# imu_middle.net
KiCad netlist of a schematic drawn in EAGLE
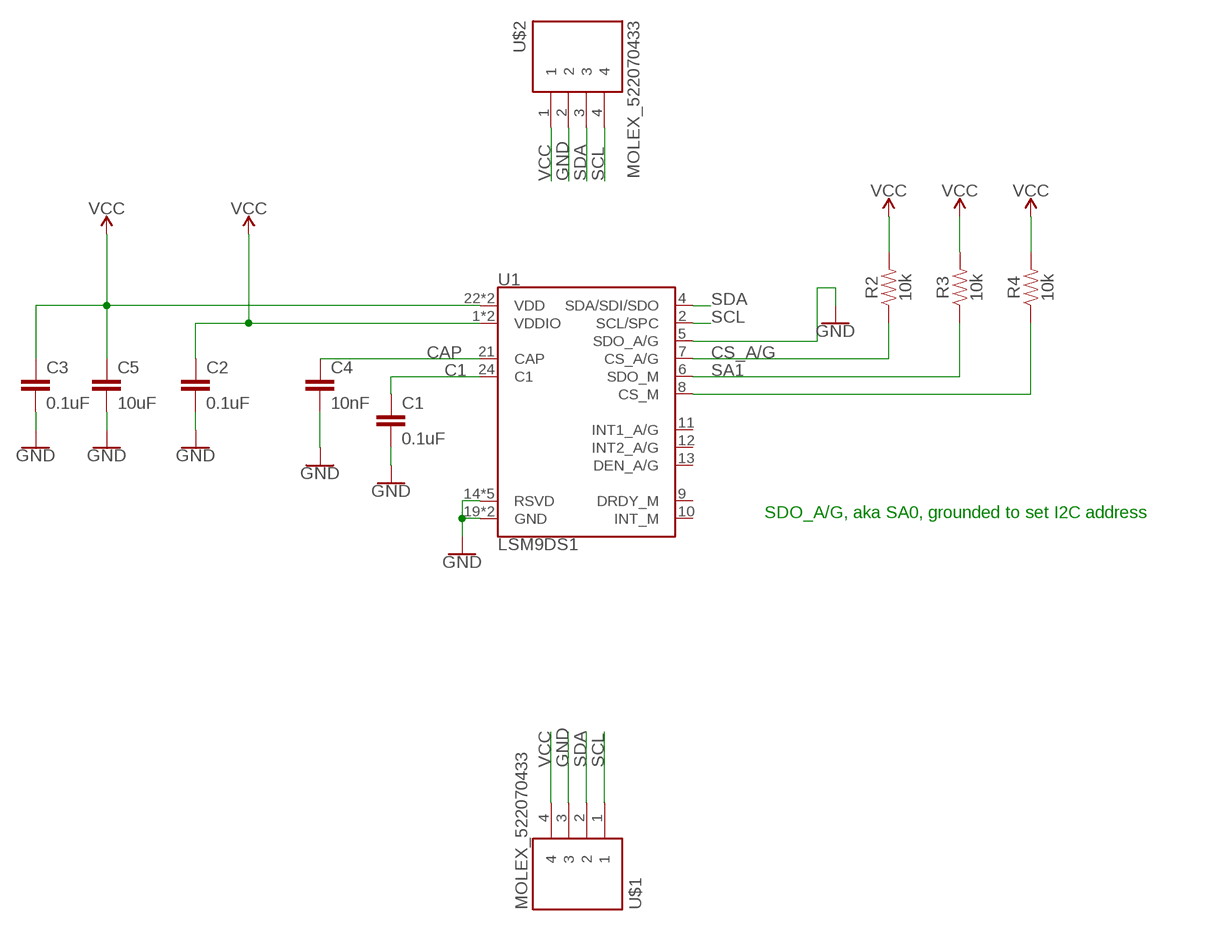
[diagram p0: schematic, sheet 1]

(export (version "E")
  (design (tool "Eeschema 10.0.6"))
  (components
    (comp (ref "C1")
      (value "0.1uF")
      (footprint "eagle-import:0603")
      (libsource (lib "eagle-import") (part "0.1UF-0603-25V-(+80/-20%)"))
    )
    (comp (ref "C2")
      (value "0.1uF")
      (footprint "eagle-import:0603")
      (libsource (lib "eagle-import") (part "0.1UF-0603-25V-(+80/-20%)"))
    )
    (comp (ref "C3")
      (value "0.1uF")
      (footprint "eagle-import:0603")
      (libsource (lib "eagle-import") (part "0.1UF-0603-25V-(+80/-20%)"))
    )
    (comp (ref "C4")
      (value "10nF")
      (footprint "eagle-import:0603")
      (libsource (lib "eagle-import") (part "10NF-0603-50V-10%"))
    )
    (comp (ref "C5")
      (value "10uF")
      (footprint "eagle-import:0603")
      (libsource (lib "eagle-import") (part "10UF-0603-6.3V-20%"))
    )
    (comp (ref "R2")
      (value "10k")
      (footprint "eagle-import:0603")
      (libsource (lib "eagle-import") (part "10KOHM-0603-1/10W-1%"))
    )
    (comp (ref "R3")
      (value "10k")
      (footprint "eagle-import:0603")
      (libsource (lib "eagle-import") (part "10KOHM-0603-1/10W-1%"))
    )
    (comp (ref "R4")
      (value "10k")
      (footprint "eagle-import:0603")
      (libsource (lib "eagle-import") (part "10KOHM-0603-1/10W-1%"))
    )
    (comp (ref "U$1")
      (value "MOLEX_522070433")
      (footprint "eagle-import:MOLEX4_1MM")
      (libsource (lib "eagle-import") (part "MOLEX_522070433"))
    )
    (comp (ref "U$2")
      (value "MOLEX_522070433")
      (footprint "eagle-import:MOLEX4_1MM")
      (libsource (lib "eagle-import") (part "MOLEX_522070433"))
    )
    (comp (ref "U1")
      (value "LSM9DS1")
      (footprint "eagle-import:LGA-24-3.5X3")
      (libsource (lib "eagle-import") (part "LSM9DS1"))
    )
  )
  (nets
    (net (code "1") (name "/C1") (class "Default")
      (node (ref "C1") (pin "1") (pinfunction "1_1") (pintype "passive"))
      (node (ref "U1") (pin "24") (pinfunction "C1_24") (pintype "bidirectional"))
    )
    (net (code "2") (name "/CAP") (class "Default")
      (node (ref "C4") (pin "1") (pinfunction "1_1") (pintype "passive"))
      (node (ref "U1") (pin "21") (pinfunction "CAP_21") (pintype "bidirectional"))
    )
    (net (code "3") (name "/CS_A{slash}G") (class "Default")
      (node (ref "R2") (pin "1") (pinfunction "1_1") (pintype "passive"))
      (node (ref "U1") (pin "7") (pinfunction "CS_A/G_7") (pintype "bidirectional"))
    )
    (net (code "4") (name "/SA1") (class "Default")
      (node (ref "R3") (pin "1") (pinfunction "1_1") (pintype "passive"))
      (node (ref "U1") (pin "6") (pinfunction "SDO_M_6") (pintype "bidirectional"))
    )
    (net (code "5") (name "/SCL") (class "Default")
      (node (ref "U$1") (pin "1") (pinfunction "1_1") (pintype "passive"))
      (node (ref "U$2") (pin "4") (pinfunction "4_4") (pintype "passive"))
      (node (ref "U1") (pin "2") (pinfunction "SCL/SPC_2") (pintype "bidirectional"))
    )
    (net (code "6") (name "/SDA") (class "Default")
      (node (ref "U$1") (pin "2") (pinfunction "2_2") (pintype "passive"))
      (node (ref "U$2") (pin "3") (pinfunction "3_3") (pintype "passive"))
      (node (ref "U1") (pin "4") (pinfunction "SDA/SDI/SDO_4") (pintype "bidirectional"))
    )
    (net (code "7") (name "GND") (class "Default")
      (node (ref "C1") (pin "2") (pinfunction "2_2") (pintype "passive"))
      (node (ref "C2") (pin "2") (pinfunction "2_2") (pintype "passive"))
      (node (ref "C3") (pin "2") (pinfunction "2_2") (pintype "passive"))
      (node (ref "C4") (pin "2") (pinfunction "2_2") (pintype "passive"))
      (node (ref "C5") (pin "2") (pinfunction "2_2") (pintype "passive"))
      (node (ref "U$1") (pin "3") (pinfunction "3_3") (pintype "passive"))
      (node (ref "U$2") (pin "2") (pinfunction "2_2") (pintype "passive"))
      (node (ref "U1") (pin "14") (pinfunction "RSVD_14") (pintype "bidirectional"))
      (node (ref "U1") (pin "15") (pinfunction "RSVD_15") (pintype "bidirectional"))
      (node (ref "U1") (pin "16") (pinfunction "RSVD_16") (pintype "bidirectional"))
      (node (ref "U1") (pin "17") (pinfunction "RSVD_17") (pintype "bidirectional"))
      (node (ref "U1") (pin "18") (pinfunction "RSVD_18") (pintype "bidirectional"))
      (node (ref "U1") (pin "19") (pinfunction "GND_19") (pintype "bidirectional"))
      (node (ref "U1") (pin "20") (pinfunction "GND_20") (pintype "bidirectional"))
      (node (ref "U1") (pin "5") (pinfunction "SDO_A/G_5") (pintype "bidirectional"))
    )
    (net (code "8") (name "Net-(U1-CS_M)") (class "Default")
      (node (ref "R4") (pin "1") (pinfunction "1_1") (pintype "passive"))
      (node (ref "U1") (pin "8") (pinfunction "CS_M_8") (pintype "bidirectional"))
    )
    (net (code "9") (name "VCC") (class "Default")
      (node (ref "C2") (pin "1") (pinfunction "1_1") (pintype "passive"))
      (node (ref "C3") (pin "1") (pinfunction "1_1") (pintype "passive"))
      (node (ref "C5") (pin "1") (pinfunction "1_1") (pintype "passive"))
      (node (ref "R2") (pin "2") (pinfunction "2_2") (pintype "passive"))
      (node (ref "R3") (pin "2") (pinfunction "2_2") (pintype "passive"))
      (node (ref "R4") (pin "2") (pinfunction "2_2") (pintype "passive"))
      (node (ref "U$1") (pin "4") (pinfunction "4_4") (pintype "passive"))
      (node (ref "U$2") (pin "1") (pinfunction "1_1") (pintype "passive"))
      (node (ref "U1") (pin "1") (pinfunction "VDDIO_1") (pintype "bidirectional"))
      (node (ref "U1") (pin "22") (pinfunction "VDD_22") (pintype "bidirectional"))
      (node (ref "U1") (pin "23") (pinfunction "VDD_23") (pintype "bidirectional"))
      (node (ref "U1") (pin "3") (pinfunction "VDDIO_3") (pintype "bidirectional"))
    )
    (net (code "10") (name "unconnected-(U1-DEN_A{slash}G-Pad13)") (class "Default")
      (node (ref "U1") (pin "13") (pinfunction "DEN_A/G_13") (pintype "bidirectional"))
    )
    (net (code "11") (name "unconnected-(U1-DRDY_M-Pad9)") (class "Default")
      (node (ref "U1") (pin "9") (pinfunction "DRDY_M_9") (pintype "bidirectional"))
    )
    (net (code "12") (name "unconnected-(U1-INT1_A{slash}G-Pad11)") (class "Default")
      (node (ref "U1") (pin "11") (pinfunction "INT1_A/G_11") (pintype "bidirectional"))
    )
    (net (code "13") (name "unconnected-(U1-INT2_A{slash}G-Pad12)") (class "Default")
      (node (ref "U1") (pin "12") (pinfunction "INT2_A/G_12") (pintype "bidirectional"))
    )
    (net (code "14") (name "unconnected-(U1-INT_M-Pad10)") (class "Default")
      (node (ref "U1") (pin "10") (pinfunction "INT_M_10") (pintype "bidirectional"))
    )
  )
)
